# slush_alt_board_rev_a.net
KiCad netlist of a schematic drawn in EAGLE
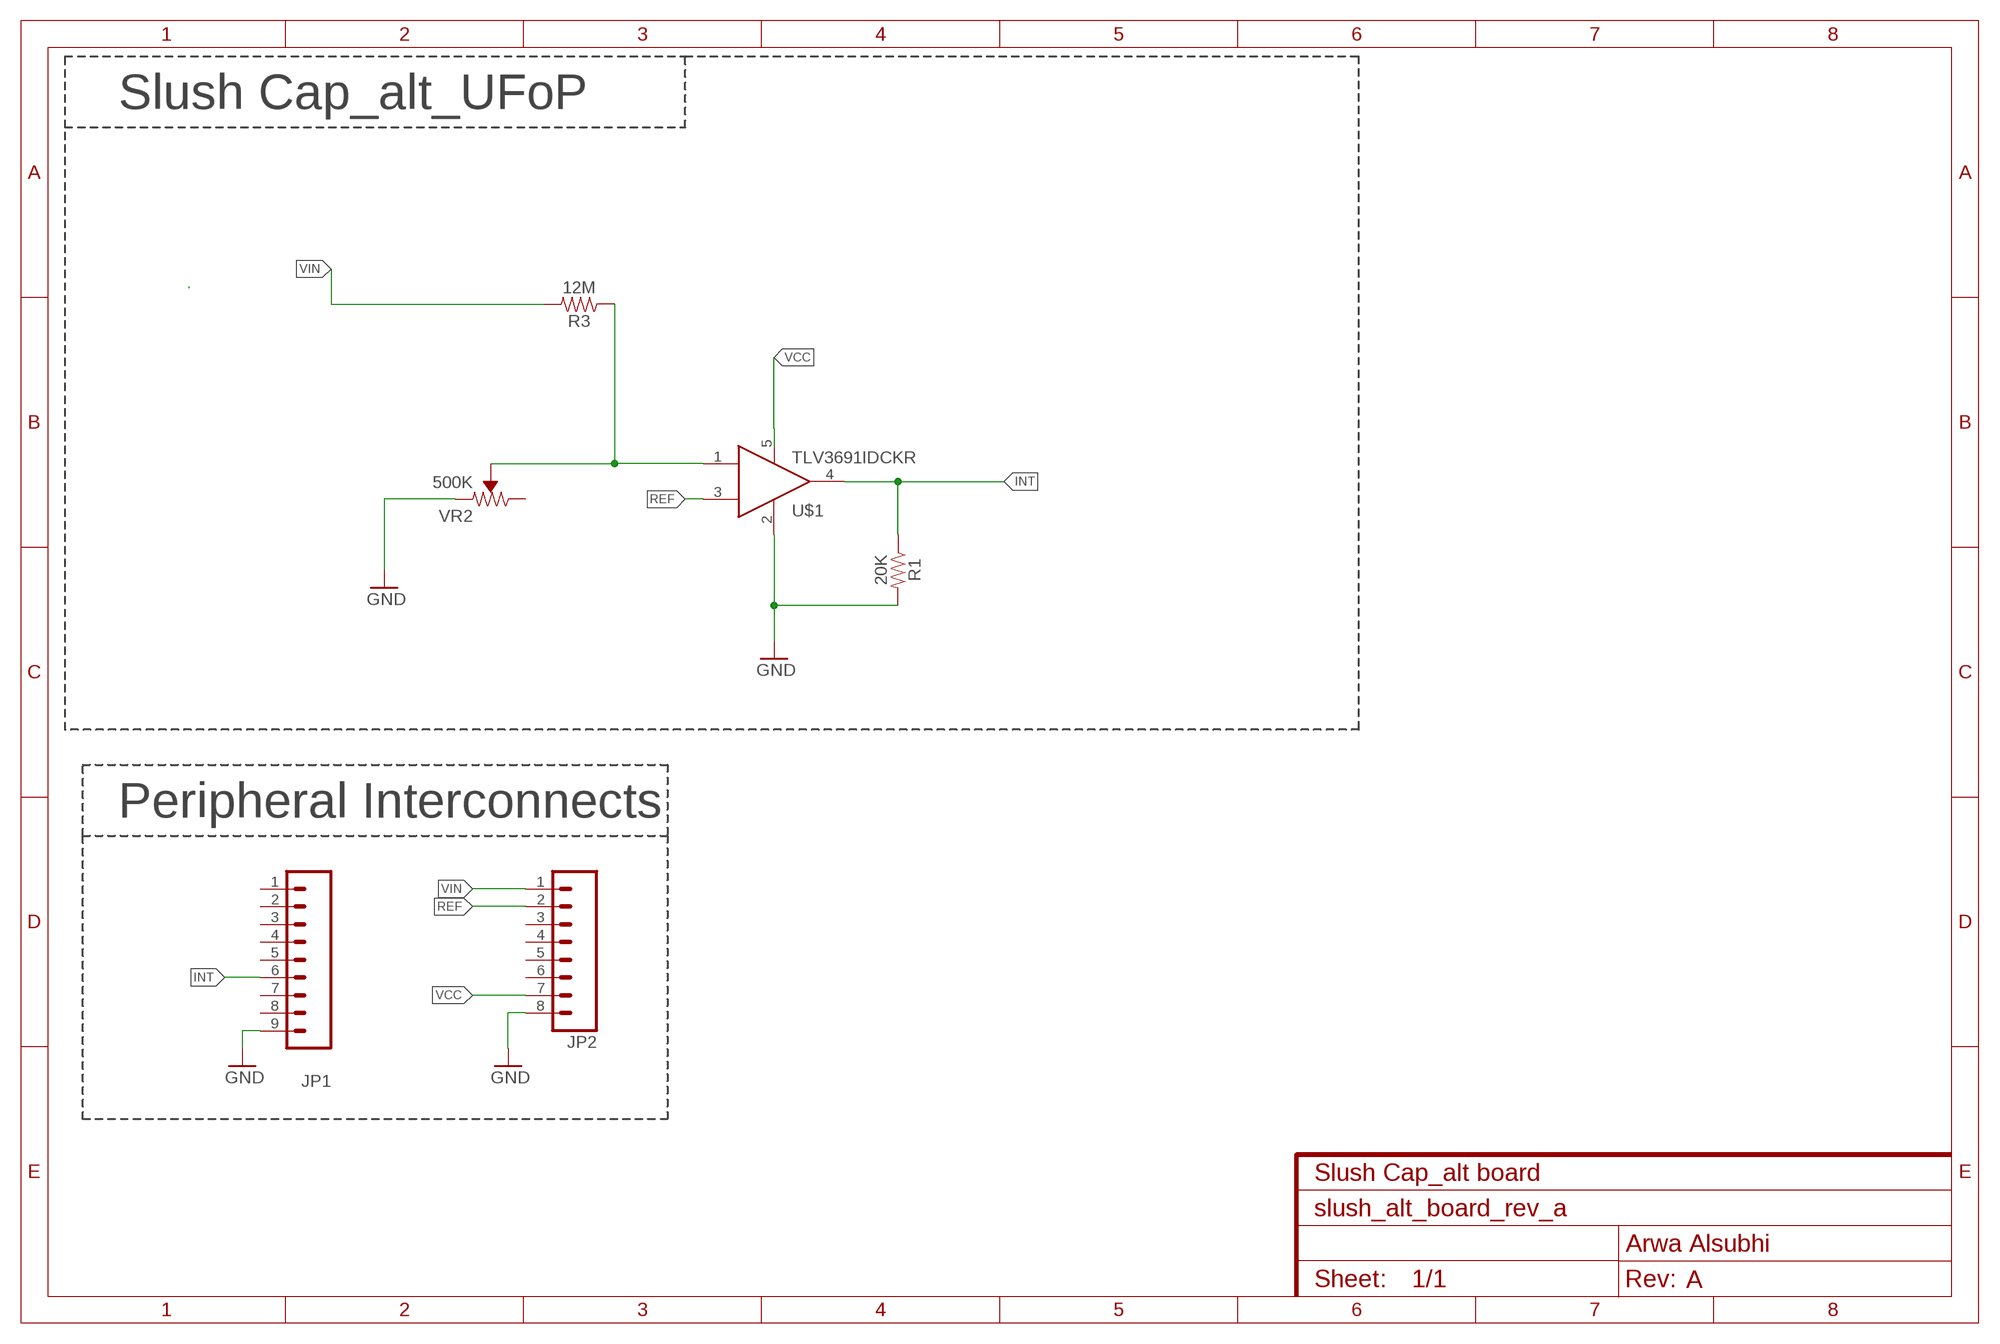
[diagram p0: schematic, sheet 1]

(export (version "E")
  (design (tool "Eeschema 10.0.6"))
  (components
    (comp (ref "JP1")
      (value "M091.27MM")
      (footprint "eagle-import:1X09-1.27MM")
      (fields (field (name "MANUFACTURERPARTNUMBER") "GRPB091VWVN-RC ") (field (name "MPN") "GRPB091VWVN-RC"))
      (libsource (lib "eagle-import") (part "M091.27MM"))
    )
    (comp (ref "JP2")
      (value "M081.27MM")
      (footprint "eagle-import:1X08-1.27MM")
      (fields (field (name "MANUFACTURERPARTNUMBER") "GRPB081VWVN-RC "))
      (libsource (lib "eagle-import") (part "M081.27MM"))
    )
    (comp (ref "R1")
      (value "20K")
      (footprint "eagle-import:0805")
      (libsource (lib "eagle-import") (part "0.3OHM-0805-1/8W-1%"))
    )
    (comp (ref "R3")
      (value "12M")
      (footprint "eagle-import:0805")
      (libsource (lib "eagle-import") (part "0.3OHM-0805-1/8W-1%"))
    )
    (comp (ref "U$1")
      (value "TLV3691IDCKR")
      (footprint "eagle-import:SOT353")
      (libsource (lib "eagle-import") (part "TLV3691IDCKR"))
    )
    (comp (ref "VR2")
      (value "500K")
      (footprint "eagle-import:TRIMPOT-SMD-3MM-CLOSED")
      (libsource (lib "eagle-import") (part "TRIMPOT-SMD-3MM-CLOSED-1/8W-20%"))
    )
  )
  (nets
    (net (code "1") (name "GND") (class "Default")
      (node (ref "JP1") (pin "9") (pinfunction "9_9") (pintype "passive"))
      (node (ref "JP2") (pin "8") (pinfunction "8_8") (pintype "passive"))
      (node (ref "R1") (pin "2") (pinfunction "2_2") (pintype "passive"))
      (node (ref "U$1") (pin "2") (pinfunction "2_2") (pintype "bidirectional"))
      (node (ref "VR2") (pin "1") (pinfunction "CCW_1") (pintype "passive"))
    )
    (net (code "2") (name "INT") (class "Default")
      (node (ref "JP1") (pin "6") (pinfunction "6_6") (pintype "passive"))
      (node (ref "R1") (pin "1") (pinfunction "1_1") (pintype "passive"))
      (node (ref "U$1") (pin "4") (pinfunction "4_4") (pintype "bidirectional"))
    )
    (net (code "3") (name "Net-(VR2-WIPER)") (class "Default")
      (node (ref "R3") (pin "1") (pinfunction "1_1") (pintype "passive"))
      (node (ref "U$1") (pin "1") (pinfunction "1_1") (pintype "bidirectional"))
      (node (ref "VR2") (pin "2") (pinfunction "WIPER_2") (pintype "passive"))
    )
    (net (code "4") (name "REF") (class "Default")
      (node (ref "JP2") (pin "2") (pinfunction "2_2") (pintype "passive"))
      (node (ref "U$1") (pin "3") (pinfunction "3_3") (pintype "bidirectional"))
    )
    (net (code "5") (name "VCC") (class "Default")
      (node (ref "JP2") (pin "7") (pinfunction "7_7") (pintype "passive"))
      (node (ref "U$1") (pin "5") (pinfunction "5_5") (pintype "bidirectional"))
    )
    (net (code "6") (name "VIN") (class "Default")
      (node (ref "JP2") (pin "1") (pinfunction "1_1") (pintype "passive"))
    )
    (net (code "7") (name "unconnected-(JP1-Pad1)") (class "Default")
      (node (ref "JP1") (pin "1") (pinfunction "1_1") (pintype "passive"))
    )
    (net (code "8") (name "unconnected-(JP1-Pad2)") (class "Default")
      (node (ref "JP1") (pin "2") (pinfunction "2_2") (pintype "passive"))
    )
    (net (code "9") (name "unconnected-(JP1-Pad3)") (class "Default")
      (node (ref "JP1") (pin "3") (pinfunction "3_3") (pintype "passive"))
    )
    (net (code "10") (name "unconnected-(JP1-Pad4)") (class "Default")
      (node (ref "JP1") (pin "4") (pinfunction "4_4") (pintype "passive"))
    )
    (net (code "11") (name "unconnected-(JP1-Pad5)") (class "Default")
      (node (ref "JP1") (pin "5") (pinfunction "5_5") (pintype "passive"))
    )
    (net (code "12") (name "unconnected-(JP1-Pad7)") (class "Default")
      (node (ref "JP1") (pin "7") (pinfunction "7_7") (pintype "passive"))
    )
    (net (code "13") (name "unconnected-(JP1-Pad8)") (class "Default")
      (node (ref "JP1") (pin "8") (pinfunction "8_8") (pintype "passive"))
    )
    (net (code "14") (name "unconnected-(JP2-Pad3)") (class "Default")
      (node (ref "JP2") (pin "3") (pinfunction "3_3") (pintype "passive"))
    )
    (net (code "15") (name "unconnected-(JP2-Pad4)") (class "Default")
      (node (ref "JP2") (pin "4") (pinfunction "4_4") (pintype "passive"))
    )
    (net (code "16") (name "unconnected-(JP2-Pad5)") (class "Default")
      (node (ref "JP2") (pin "5") (pinfunction "5_5") (pintype "passive"))
    )
    (net (code "17") (name "unconnected-(JP2-Pad6)") (class "Default")
      (node (ref "JP2") (pin "6") (pinfunction "6_6") (pintype "passive"))
    )
    (net (code "18") (name "unconnected-(R3-Pad2)") (class "Default")
      (node (ref "R3") (pin "2") (pinfunction "2_2") (pintype "passive"))
    )
    (net (code "19") (name "unconnected-(VR2-CW-Pad3)") (class "Default")
      (node (ref "VR2") (pin "3") (pinfunction "CW_3") (pintype "passive"))
    )
  )
)
